# display.net
KiCad netlist of a schematic drawn in EAGLE
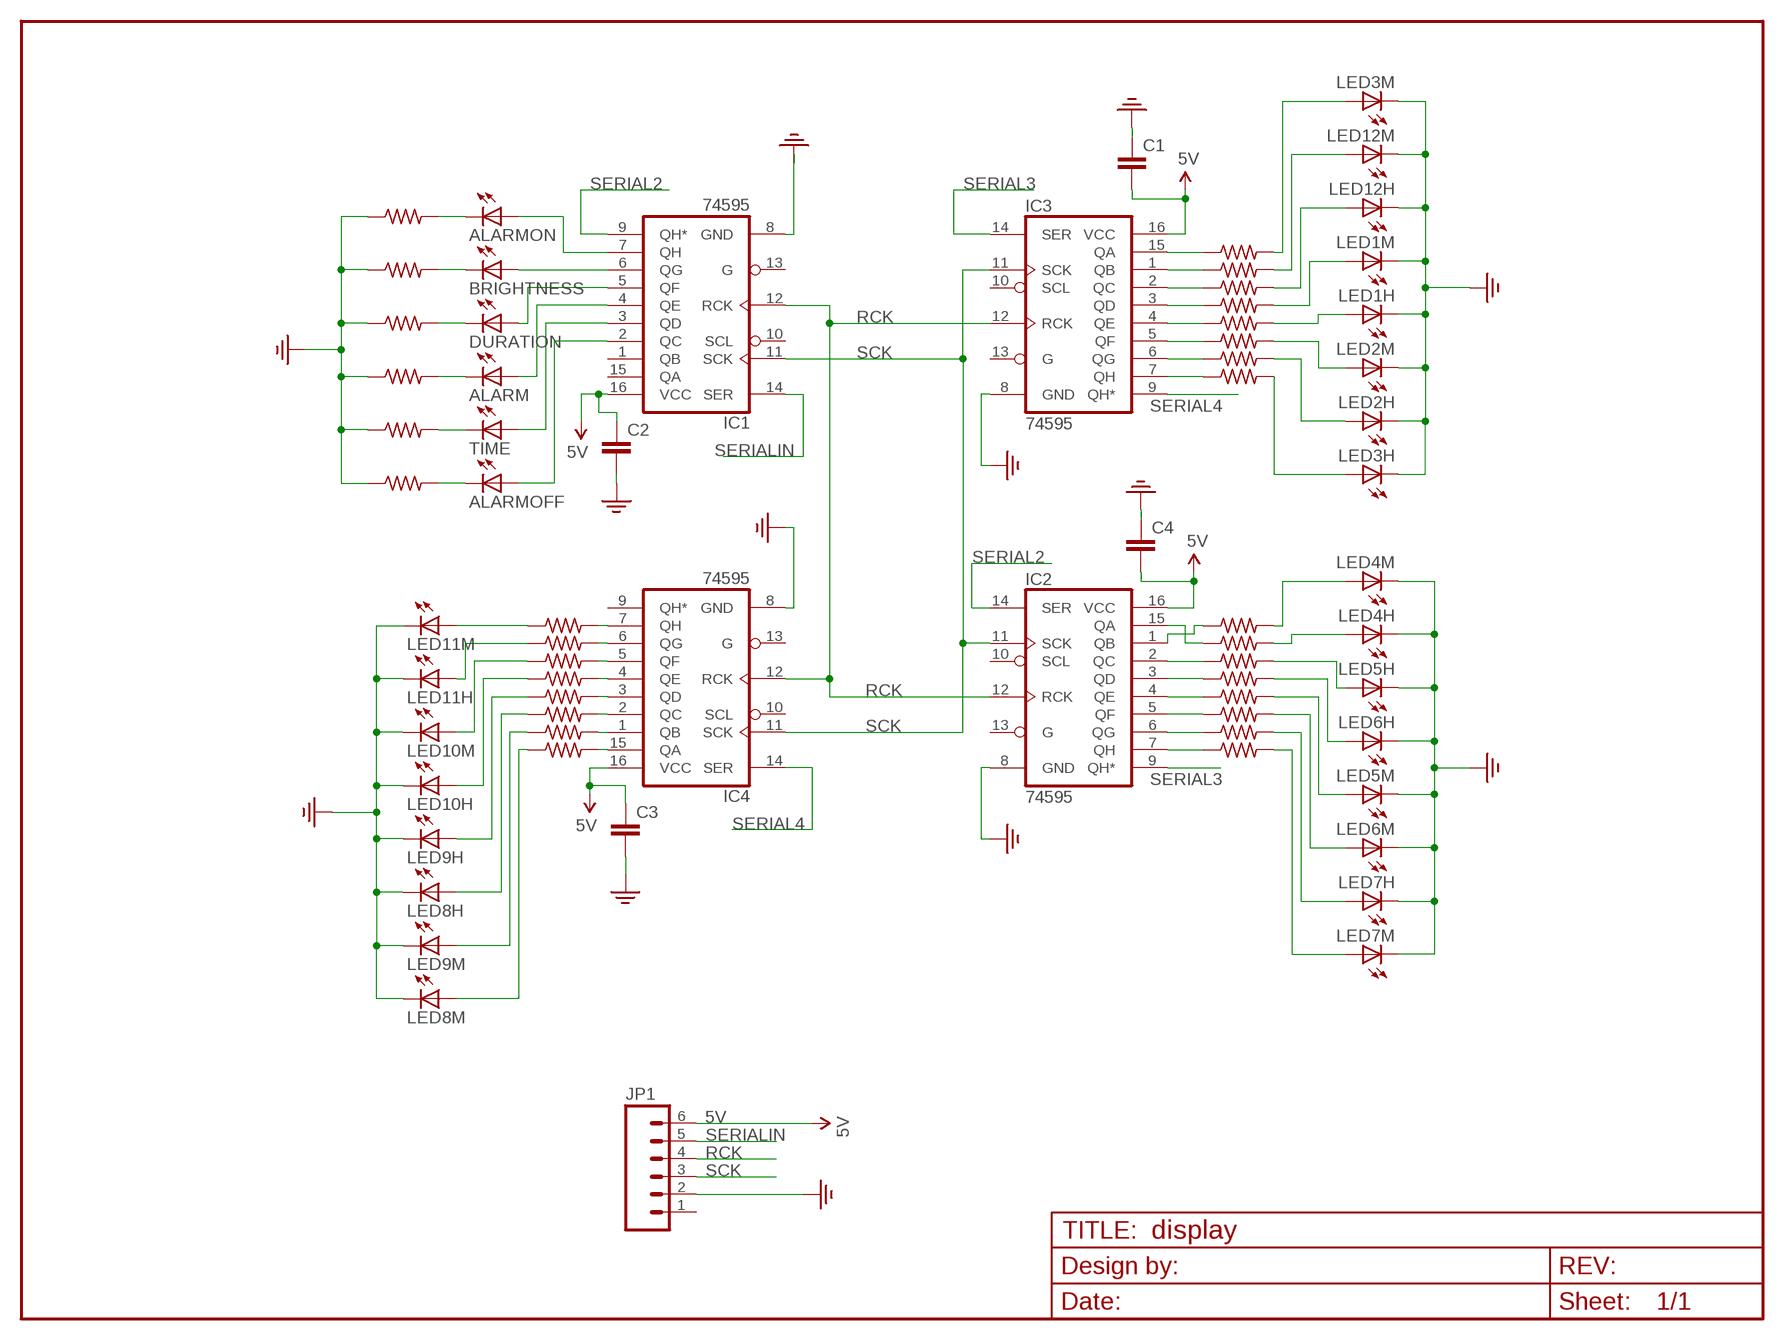
[diagram p0: schematic, sheet 1]

(export (version "E")
  (design (tool "Eeschema 10.0.6"))
  (components
    (comp (ref "ALARM")
      (value "LED1206")
      (footprint "eagle-import:LED-1206")
      (libsource (lib "eagle-import") (part "LED1206"))
    )
    (comp (ref "ALARMOFF")
      (value "LED1206")
      (footprint "eagle-import:LED-1206")
      (libsource (lib "eagle-import") (part "LED1206"))
    )
    (comp (ref "ALARMON")
      (value "LED1206")
      (footprint "eagle-import:LED-1206")
      (libsource (lib "eagle-import") (part "LED1206"))
    )
    (comp (ref "BRIGHTNESS")
      (value "LED1206")
      (footprint "eagle-import:LED-1206")
      (libsource (lib "eagle-import") (part "LED1206"))
    )
    (comp (ref "C1")
      (value "CAP0805")
      (footprint "eagle-import:0805")
      (libsource (lib "eagle-import") (part "CAP0805"))
    )
    (comp (ref "C2")
      (value "CAP0805")
      (footprint "eagle-import:0805")
      (libsource (lib "eagle-import") (part "CAP0805"))
    )
    (comp (ref "C3")
      (value "CAP0805")
      (footprint "eagle-import:0805")
      (libsource (lib "eagle-import") (part "CAP0805"))
    )
    (comp (ref "C4")
      (value "CAP0805")
      (footprint "eagle-import:0805")
      (libsource (lib "eagle-import") (part "CAP0805"))
    )
    (comp (ref "DURATION")
      (value "LED1206")
      (footprint "eagle-import:LED-1206")
      (libsource (lib "eagle-import") (part "LED1206"))
    )
    (comp (ref "FRAME1")
      (value "FRAME-LETTER")
      (footprint "eagle-import:CREATIVE_COMMONS")
      (libsource (lib "eagle-import") (part "FRAME-LETTER"))
    )
    (comp (ref "IC1")
      (value "74595")
      (footprint "eagle-import:TSSOP16")
      (libsource (lib "eagle-import") (part "74595"))
    )
    (comp (ref "IC2")
      (value "74595")
      (footprint "eagle-import:TSSOP16")
      (libsource (lib "eagle-import") (part "74595"))
    )
    (comp (ref "IC3")
      (value "74595")
      (footprint "eagle-import:TSSOP16")
      (libsource (lib "eagle-import") (part "74595"))
    )
    (comp (ref "IC4")
      (value "74595")
      (footprint "eagle-import:TSSOP16")
      (libsource (lib "eagle-import") (part "74595"))
    )
    (comp (ref "JP1")
      (value "M06SIP")
      (footprint "eagle-import:1X06")
      (libsource (lib "eagle-import") (part "M06SIP"))
    )
    (comp (ref "LED1H")
      (value "LED1206")
      (footprint "eagle-import:LED-1206")
      (libsource (lib "eagle-import") (part "LED1206"))
    )
    (comp (ref "LED1M")
      (value "LED1206")
      (footprint "eagle-import:LED-1206")
      (libsource (lib "eagle-import") (part "LED1206"))
    )
    (comp (ref "LED2H")
      (value "LED1206")
      (footprint "eagle-import:LED-1206")
      (libsource (lib "eagle-import") (part "LED1206"))
    )
    (comp (ref "LED2M")
      (value "LED1206")
      (footprint "eagle-import:LED-1206")
      (libsource (lib "eagle-import") (part "LED1206"))
    )
    (comp (ref "LED3H")
      (value "LED1206")
      (footprint "eagle-import:LED-1206")
      (libsource (lib "eagle-import") (part "LED1206"))
    )
    (comp (ref "LED3M")
      (value "LED1206")
      (footprint "eagle-import:LED-1206")
      (libsource (lib "eagle-import") (part "LED1206"))
    )
    (comp (ref "LED4H")
      (value "LED1206")
      (footprint "eagle-import:LED-1206")
      (libsource (lib "eagle-import") (part "LED1206"))
    )
    (comp (ref "LED4M")
      (value "LED1206")
      (footprint "eagle-import:LED-1206")
      (libsource (lib "eagle-import") (part "LED1206"))
    )
    (comp (ref "LED5H")
      (value "LED1206")
      (footprint "eagle-import:LED-1206")
      (libsource (lib "eagle-import") (part "LED1206"))
    )
    (comp (ref "LED5M")
      (value "LED1206")
      (footprint "eagle-import:LED-1206")
      (libsource (lib "eagle-import") (part "LED1206"))
    )
    (comp (ref "LED6H")
      (value "LED1206")
      (footprint "eagle-import:LED-1206")
      (libsource (lib "eagle-import") (part "LED1206"))
    )
    (comp (ref "LED6M")
      (value "LED1206")
      (footprint "eagle-import:LED-1206")
      (libsource (lib "eagle-import") (part "LED1206"))
    )
    (comp (ref "LED7H")
      (value "LED1206")
      (footprint "eagle-import:LED-1206")
      (libsource (lib "eagle-import") (part "LED1206"))
    )
    (comp (ref "LED7M")
      (value "LED1206")
      (footprint "eagle-import:LED-1206")
      (libsource (lib "eagle-import") (part "LED1206"))
    )
    (comp (ref "LED8H")
      (value "LED1206")
      (footprint "eagle-import:LED-1206")
      (libsource (lib "eagle-import") (part "LED1206"))
    )
    (comp (ref "LED8M")
      (value "LED1206")
      (footprint "eagle-import:LED-1206")
      (libsource (lib "eagle-import") (part "LED1206"))
    )
    (comp (ref "LED9H")
      (value "LED1206")
      (footprint "eagle-import:LED-1206")
      (libsource (lib "eagle-import") (part "LED1206"))
    )
    (comp (ref "LED9M")
      (value "LED1206")
      (footprint "eagle-import:LED-1206")
      (libsource (lib "eagle-import") (part "LED1206"))
    )
    (comp (ref "LED10H")
      (value "LED1206")
      (footprint "eagle-import:LED-1206")
      (libsource (lib "eagle-import") (part "LED1206"))
    )
    (comp (ref "LED10M")
      (value "LED1206")
      (footprint "eagle-import:LED-1206")
      (libsource (lib "eagle-import") (part "LED1206"))
    )
    (comp (ref "LED11H")
      (value "LED1206")
      (footprint "eagle-import:LED-1206")
      (libsource (lib "eagle-import") (part "LED1206"))
    )
    (comp (ref "LED11M")
      (value "LED1206")
      (footprint "eagle-import:LED-1206")
      (libsource (lib "eagle-import") (part "LED1206"))
    )
    (comp (ref "LED12H")
      (value "LED1206")
      (footprint "eagle-import:LED-1206")
      (libsource (lib "eagle-import") (part "LED1206"))
    )
    (comp (ref "LED12M")
      (value "LED1206")
      (footprint "eagle-import:LED-1206")
      (libsource (lib "eagle-import") (part "LED1206"))
    )
    (comp (ref "TIME")
      (value "LED1206")
      (footprint "eagle-import:LED-1206")
      (libsource (lib "eagle-import") (part "LED1206"))
    )
    (comp (ref "U$2")
      (value "RESISTOR")
      (footprint "eagle-import:RESISTOR-0805")
      (libsource (lib "eagle-import") (part "RESISTOR"))
    )
    (comp (ref "U$3")
      (value "RESISTOR")
      (footprint "eagle-import:RESISTOR-0805")
      (libsource (lib "eagle-import") (part "RESISTOR"))
    )
    (comp (ref "U$6")
      (value "RESISTOR")
      (footprint "eagle-import:RESISTOR-0805")
      (libsource (lib "eagle-import") (part "RESISTOR"))
    )
    (comp (ref "U$7")
      (value "RESISTOR")
      (footprint "eagle-import:RESISTOR-0805")
      (libsource (lib "eagle-import") (part "RESISTOR"))
    )
    (comp (ref "U$8")
      (value "RESISTOR")
      (footprint "eagle-import:RESISTOR-0805")
      (libsource (lib "eagle-import") (part "RESISTOR"))
    )
    (comp (ref "U$9")
      (value "RESISTOR")
      (footprint "eagle-import:RESISTOR-0805")
      (libsource (lib "eagle-import") (part "RESISTOR"))
    )
    (comp (ref "U$10")
      (value "RESISTOR")
      (footprint "eagle-import:RESISTOR-0805")
      (libsource (lib "eagle-import") (part "RESISTOR"))
    )
    (comp (ref "U$11")
      (value "RESISTOR")
      (footprint "eagle-import:RESISTOR-0805")
      (libsource (lib "eagle-import") (part "RESISTOR"))
    )
    (comp (ref "U$12")
      (value "RESISTOR")
      (footprint "eagle-import:RESISTOR-0805")
      (libsource (lib "eagle-import") (part "RESISTOR"))
    )
    (comp (ref "U$13")
      (value "RESISTOR")
      (footprint "eagle-import:RESISTOR-0805")
      (libsource (lib "eagle-import") (part "RESISTOR"))
    )
    (comp (ref "U$14")
      (value "RESISTOR")
      (footprint "eagle-import:RESISTOR-0805")
      (libsource (lib "eagle-import") (part "RESISTOR"))
    )
    (comp (ref "U$15")
      (value "RESISTOR")
      (footprint "eagle-import:RESISTOR-0805")
      (libsource (lib "eagle-import") (part "RESISTOR"))
    )
    (comp (ref "U$16")
      (value "RESISTOR")
      (footprint "eagle-import:RESISTOR-0805")
      (libsource (lib "eagle-import") (part "RESISTOR"))
    )
    (comp (ref "U$17")
      (value "RESISTOR")
      (footprint "eagle-import:RESISTOR-0805")
      (libsource (lib "eagle-import") (part "RESISTOR"))
    )
    (comp (ref "U$18")
      (value "RESISTOR")
      (footprint "eagle-import:RESISTOR-0805")
      (libsource (lib "eagle-import") (part "RESISTOR"))
    )
    (comp (ref "U$19")
      (value "RESISTOR")
      (footprint "eagle-import:RESISTOR-0805")
      (libsource (lib "eagle-import") (part "RESISTOR"))
    )
    (comp (ref "U$20")
      (value "RESISTOR")
      (footprint "eagle-import:RESISTOR-0805")
      (libsource (lib "eagle-import") (part "RESISTOR"))
    )
    (comp (ref "U$21")
      (value "RESISTOR")
      (footprint "eagle-import:RESISTOR-0805")
      (libsource (lib "eagle-import") (part "RESISTOR"))
    )
    (comp (ref "U$22")
      (value "RESISTOR")
      (footprint "eagle-import:RESISTOR-0805")
      (libsource (lib "eagle-import") (part "RESISTOR"))
    )
    (comp (ref "U$23")
      (value "RESISTOR")
      (footprint "eagle-import:RESISTOR-0805")
      (libsource (lib "eagle-import") (part "RESISTOR"))
    )
    (comp (ref "U$24")
      (value "RESISTOR")
      (footprint "eagle-import:RESISTOR-0805")
      (libsource (lib "eagle-import") (part "RESISTOR"))
    )
    (comp (ref "U$25")
      (value "RESISTOR")
      (footprint "eagle-import:RESISTOR-0805")
      (libsource (lib "eagle-import") (part "RESISTOR"))
    )
    (comp (ref "U$26")
      (value "RESISTOR")
      (footprint "eagle-import:RESISTOR-0805")
      (libsource (lib "eagle-import") (part "RESISTOR"))
    )
    (comp (ref "U$27")
      (value "RESISTOR")
      (footprint "eagle-import:RESISTOR-0805")
      (libsource (lib "eagle-import") (part "RESISTOR"))
    )
    (comp (ref "U$28")
      (value "RESISTOR")
      (footprint "eagle-import:RESISTOR-0805")
      (libsource (lib "eagle-import") (part "RESISTOR"))
    )
    (comp (ref "U$29")
      (value "RESISTOR")
      (footprint "eagle-import:RESISTOR-0805")
      (libsource (lib "eagle-import") (part "RESISTOR"))
    )
    (comp (ref "U$30")
      (value "RESISTOR")
      (footprint "eagle-import:RESISTOR-0805")
      (libsource (lib "eagle-import") (part "RESISTOR"))
    )
    (comp (ref "U$31")
      (value "RESISTOR")
      (footprint "eagle-import:RESISTOR-0805")
      (libsource (lib "eagle-import") (part "RESISTOR"))
    )
    (comp (ref "U$32")
      (value "RESISTOR")
      (footprint "eagle-import:RESISTOR-0805")
      (libsource (lib "eagle-import") (part "RESISTOR"))
    )
    (comp (ref "U$33")
      (value "RESISTOR")
      (footprint "eagle-import:RESISTOR-0805")
      (libsource (lib "eagle-import") (part "RESISTOR"))
    )
  )
  (nets
    (net (code "1") (name "/RCK") (class "Default")
      (node (ref "IC1") (pin "12") (pinfunction "RCK_12") (pintype "input"))
      (node (ref "IC2") (pin "12") (pinfunction "RCK_12") (pintype "input"))
      (node (ref "IC3") (pin "12") (pinfunction "RCK_12") (pintype "input"))
      (node (ref "IC4") (pin "12") (pinfunction "RCK_12") (pintype "input"))
      (node (ref "JP1") (pin "4") (pinfunction "4_4") (pintype "passive"))
    )
    (net (code "2") (name "/SCK") (class "Default")
      (node (ref "IC1") (pin "11") (pinfunction "SCK_11") (pintype "input"))
      (node (ref "IC2") (pin "11") (pinfunction "SCK_11") (pintype "input"))
      (node (ref "IC3") (pin "11") (pinfunction "SCK_11") (pintype "input"))
      (node (ref "IC4") (pin "11") (pinfunction "SCK_11") (pintype "input"))
      (node (ref "JP1") (pin "3") (pinfunction "3_3") (pintype "passive"))
    )
    (net (code "3") (name "/SERIAL2") (class "Default")
      (node (ref "IC1") (pin "9") (pinfunction "QH*_9") (pintype "output"))
      (node (ref "IC2") (pin "14") (pinfunction "SER_14") (pintype "input"))
    )
    (net (code "4") (name "/SERIAL3") (class "Default")
      (node (ref "IC2") (pin "9") (pinfunction "QH*_9") (pintype "output"))
      (node (ref "IC3") (pin "14") (pinfunction "SER_14") (pintype "input"))
    )
    (net (code "5") (name "/SERIAL4") (class "Default")
      (node (ref "IC3") (pin "9") (pinfunction "QH*_9") (pintype "output"))
      (node (ref "IC4") (pin "14") (pinfunction "SER_14") (pintype "input"))
    )
    (net (code "6") (name "/SERIALIN") (class "Default")
      (node (ref "IC1") (pin "14") (pinfunction "SER_14") (pintype "input"))
      (node (ref "JP1") (pin "5") (pinfunction "5_5") (pintype "passive"))
    )
    (net (code "7") (name "5V") (class "Default")
      (node (ref "C1") (pin "2") (pinfunction "2_2") (pintype "passive"))
      (node (ref "C2") (pin "1") (pinfunction "1_1") (pintype "passive"))
      (node (ref "C3") (pin "1") (pinfunction "1_1") (pintype "passive"))
      (node (ref "C4") (pin "2") (pinfunction "2_2") (pintype "passive"))
      (node (ref "IC1") (pin "16") (pinfunction "VCC_16") (pintype "power_in"))
      (node (ref "IC2") (pin "16") (pinfunction "VCC_16") (pintype "power_in"))
      (node (ref "IC3") (pin "16") (pinfunction "VCC_16") (pintype "power_in"))
      (node (ref "IC4") (pin "16") (pinfunction "VCC_16") (pintype "power_in"))
      (node (ref "JP1") (pin "6") (pinfunction "6_6") (pintype "passive"))
    )
    (net (code "8") (name "GND2") (class "Default")
      (node (ref "C1") (pin "1") (pinfunction "1_1") (pintype "passive"))
      (node (ref "C2") (pin "2") (pinfunction "2_2") (pintype "passive"))
      (node (ref "C3") (pin "2") (pinfunction "2_2") (pintype "passive"))
      (node (ref "C4") (pin "1") (pinfunction "1_1") (pintype "passive"))
      (node (ref "IC1") (pin "8") (pinfunction "GND_8") (pintype "power_in"))
      (node (ref "IC2") (pin "8") (pinfunction "GND_8") (pintype "power_in"))
      (node (ref "IC3") (pin "8") (pinfunction "GND_8") (pintype "power_in"))
      (node (ref "IC4") (pin "8") (pinfunction "GND_8") (pintype "power_in"))
      (node (ref "JP1") (pin "2") (pinfunction "2_2") (pintype "passive"))
      (node (ref "LED10H") (pin "C") (pinfunction "C_C") (pintype "passive"))
      (node (ref "LED10M") (pin "C") (pinfunction "C_C") (pintype "passive"))
      (node (ref "LED11H") (pin "C") (pinfunction "C_C") (pintype "passive"))
      (node (ref "LED11M") (pin "C") (pinfunction "C_C") (pintype "passive"))
      (node (ref "LED12H") (pin "C") (pinfunction "C_C") (pintype "passive"))
      (node (ref "LED12M") (pin "C") (pinfunction "C_C") (pintype "passive"))
      (node (ref "LED1H") (pin "C") (pinfunction "C_C") (pintype "passive"))
      (node (ref "LED1M") (pin "C") (pinfunction "C_C") (pintype "passive"))
      (node (ref "LED2H") (pin "C") (pinfunction "C_C") (pintype "passive"))
      (node (ref "LED2M") (pin "C") (pinfunction "C_C") (pintype "passive"))
      (node (ref "LED3H") (pin "C") (pinfunction "C_C") (pintype "passive"))
      (node (ref "LED3M") (pin "C") (pinfunction "C_C") (pintype "passive"))
      (node (ref "LED4H") (pin "C") (pinfunction "C_C") (pintype "passive"))
      (node (ref "LED4M") (pin "C") (pinfunction "C_C") (pintype "passive"))
      (node (ref "LED5H") (pin "C") (pinfunction "C_C") (pintype "passive"))
      (node (ref "LED5M") (pin "C") (pinfunction "C_C") (pintype "passive"))
      (node (ref "LED6H") (pin "C") (pinfunction "C_C") (pintype "passive"))
      (node (ref "LED6M") (pin "C") (pinfunction "C_C") (pintype "passive"))
      (node (ref "LED7H") (pin "C") (pinfunction "C_C") (pintype "passive"))
      (node (ref "LED7M") (pin "C") (pinfunction "C_C") (pintype "passive"))
      (node (ref "LED8H") (pin "C") (pinfunction "C_C") (pintype "passive"))
      (node (ref "LED8M") (pin "C") (pinfunction "C_C") (pintype "passive"))
      (node (ref "LED9H") (pin "C") (pinfunction "C_C") (pintype "passive"))
      (node (ref "LED9M") (pin "C") (pinfunction "C_C") (pintype "passive"))
      (node (ref "U$24") (pin "1") (pinfunction "1_1") (pintype "passive"))
      (node (ref "U$25") (pin "1") (pinfunction "1_1") (pintype "passive"))
      (node (ref "U$30") (pin "1") (pinfunction "1_1") (pintype "passive"))
      (node (ref "U$31") (pin "1") (pinfunction "1_1") (pintype "passive"))
      (node (ref "U$32") (pin "1") (pinfunction "1_1") (pintype "passive"))
      (node (ref "U$33") (pin "1") (pinfunction "1_1") (pintype "passive"))
    )
    (net (code "9") (name "Net-(ALARM-PadC)") (class "Default")
      (node (ref "ALARM") (pin "C") (pinfunction "C_C") (pintype "passive"))
      (node (ref "U$31") (pin "2") (pinfunction "2_2") (pintype "passive"))
    )
    (net (code "10") (name "Net-(ALARMOFF-PadC)") (class "Default")
      (node (ref "ALARMOFF") (pin "C") (pinfunction "C_C") (pintype "passive"))
      (node (ref "U$33") (pin "2") (pinfunction "2_2") (pintype "passive"))
    )
    (net (code "11") (name "Net-(ALARMON-PadC)") (class "Default")
      (node (ref "ALARMON") (pin "C") (pinfunction "C_C") (pintype "passive"))
      (node (ref "U$24") (pin "2") (pinfunction "2_2") (pintype "passive"))
    )
    (net (code "12") (name "Net-(BRIGHTNESS-PadC)") (class "Default")
      (node (ref "BRIGHTNESS") (pin "C") (pinfunction "C_C") (pintype "passive"))
      (node (ref "U$25") (pin "2") (pinfunction "2_2") (pintype "passive"))
    )
    (net (code "13") (name "Net-(DURATION-PadC)") (class "Default")
      (node (ref "DURATION") (pin "C") (pinfunction "C_C") (pintype "passive"))
      (node (ref "U$30") (pin "2") (pinfunction "2_2") (pintype "passive"))
    )
    (net (code "14") (name "Net-(IC1-QC)") (class "Default")
      (node (ref "ALARMOFF") (pin "A") (pinfunction "A_A") (pintype "passive"))
      (node (ref "IC1") (pin "2") (pinfunction "QC_2") (pintype "tri_state"))
    )
    (net (code "15") (name "Net-(IC1-QD)") (class "Default")
      (node (ref "IC1") (pin "3") (pinfunction "QD_3") (pintype "tri_state"))
      (node (ref "TIME") (pin "A") (pinfunction "A_A") (pintype "passive"))
    )
    (net (code "16") (name "Net-(IC1-QE)") (class "Default")
      (node (ref "ALARM") (pin "A") (pinfunction "A_A") (pintype "passive"))
      (node (ref "IC1") (pin "4") (pinfunction "QE_4") (pintype "tri_state"))
    )
    (net (code "17") (name "Net-(IC1-QF)") (class "Default")
      (node (ref "DURATION") (pin "A") (pinfunction "A_A") (pintype "passive"))
      (node (ref "IC1") (pin "5") (pinfunction "QF_5") (pintype "tri_state"))
    )
    (net (code "18") (name "Net-(IC1-QG)") (class "Default")
      (node (ref "BRIGHTNESS") (pin "A") (pinfunction "A_A") (pintype "passive"))
      (node (ref "IC1") (pin "6") (pinfunction "QG_6") (pintype "tri_state"))
    )
    (net (code "19") (name "Net-(IC1-QH)") (class "Default")
      (node (ref "ALARMON") (pin "A") (pinfunction "A_A") (pintype "passive"))
      (node (ref "IC1") (pin "7") (pinfunction "QH_7") (pintype "tri_state"))
    )
    (net (code "20") (name "Net-(IC2-QA)") (class "Default")
      (node (ref "IC2") (pin "15") (pinfunction "QA_15") (pintype "tri_state"))
      (node (ref "U$21") (pin "1") (pinfunction "1_1") (pintype "passive"))
    )
    (net (code "21") (name "Net-(IC2-QB)") (class "Default")
      (node (ref "IC2") (pin "1") (pinfunction "QB_1") (pintype "tri_state"))
      (node (ref "U$20") (pin "1") (pinfunction "1_1") (pintype "passive"))
    )
    (net (code "22") (name "Net-(IC2-QC)") (class "Default")
      (node (ref "IC2") (pin "2") (pinfunction "QC_2") (pintype "tri_state"))
      (node (ref "U$22") (pin "1") (pinfunction "1_1") (pintype "passive"))
    )
    (net (code "23") (name "Net-(IC2-QD)") (class "Default")
      (node (ref "IC2") (pin "3") (pinfunction "QD_3") (pintype "tri_state"))
      (node (ref "U$23") (pin "1") (pinfunction "1_1") (pintype "passive"))
    )
    (net (code "24") (name "Net-(IC2-QE)") (class "Default")
      (node (ref "IC2") (pin "4") (pinfunction "QE_4") (pintype "tri_state"))
      (node (ref "U$26") (pin "1") (pinfunction "1_1") (pintype "passive"))
    )
    (net (code "25") (name "Net-(IC2-QF)") (class "Default")
      (node (ref "IC2") (pin "5") (pinfunction "QF_5") (pintype "tri_state"))
      (node (ref "U$27") (pin "1") (pinfunction "1_1") (pintype "passive"))
    )
    (net (code "26") (name "Net-(IC2-QG)") (class "Default")
      (node (ref "IC2") (pin "6") (pinfunction "QG_6") (pintype "tri_state"))
      (node (ref "U$28") (pin "1") (pinfunction "1_1") (pintype "passive"))
    )
    (net (code "27") (name "Net-(IC2-QH)") (class "Default")
      (node (ref "IC2") (pin "7") (pinfunction "QH_7") (pintype "tri_state"))
      (node (ref "U$29") (pin "1") (pinfunction "1_1") (pintype "passive"))
    )
    (net (code "28") (name "Net-(IC3-QA)") (class "Default")
      (node (ref "IC3") (pin "15") (pinfunction "QA_15") (pintype "tri_state"))
      (node (ref "U$6") (pin "1") (pinfunction "1_1") (pintype "passive"))
    )
    (net (code "29") (name "Net-(IC3-QB)") (class "Default")
      (node (ref "IC3") (pin "1") (pinfunction "QB_1") (pintype "tri_state"))
      (node (ref "U$7") (pin "1") (pinfunction "1_1") (pintype "passive"))
    )
    (net (code "30") (name "Net-(IC3-QC)") (class "Default")
      (node (ref "IC3") (pin "2") (pinfunction "QC_2") (pintype "tri_state"))
      (node (ref "U$8") (pin "1") (pinfunction "1_1") (pintype "passive"))
    )
    (net (code "31") (name "Net-(IC3-QD)") (class "Default")
      (node (ref "IC3") (pin "3") (pinfunction "QD_3") (pintype "tri_state"))
      (node (ref "U$9") (pin "1") (pinfunction "1_1") (pintype "passive"))
    )
    (net (code "32") (name "Net-(IC3-QE)") (class "Default")
      (node (ref "IC3") (pin "4") (pinfunction "QE_4") (pintype "tri_state"))
      (node (ref "U$10") (pin "1") (pinfunction "1_1") (pintype "passive"))
    )
    (net (code "33") (name "Net-(IC3-QF)") (class "Default")
      (node (ref "IC3") (pin "5") (pinfunction "QF_5") (pintype "tri_state"))
      (node (ref "U$11") (pin "1") (pinfunction "1_1") (pintype "passive"))
    )
    (net (code "34") (name "Net-(IC3-QG)") (class "Default")
      (node (ref "IC3") (pin "6") (pinfunction "QG_6") (pintype "tri_state"))
      (node (ref "U$13") (pin "1") (pinfunction "1_1") (pintype "passive"))
    )
    (net (code "35") (name "Net-(IC3-QH)") (class "Default")
      (node (ref "IC3") (pin "7") (pinfunction "QH_7") (pintype "tri_state"))
      (node (ref "U$12") (pin "1") (pinfunction "1_1") (pintype "passive"))
    )
    (net (code "36") (name "Net-(IC4-QA)") (class "Default")
      (node (ref "IC4") (pin "15") (pinfunction "QA_15") (pintype "tri_state"))
      (node (ref "U$2") (pin "2") (pinfunction "2_2") (pintype "passive"))
    )
    (net (code "37") (name "Net-(IC4-QB)") (class "Default")
      (node (ref "IC4") (pin "1") (pinfunction "QB_1") (pintype "tri_state"))
      (node (ref "U$3") (pin "2") (pinfunction "2_2") (pintype "passive"))
    )
    (net (code "38") (name "Net-(IC4-QC)") (class "Default")
      (node (ref "IC4") (pin "2") (pinfunction "QC_2") (pintype "tri_state"))
      (node (ref "U$14") (pin "2") (pinfunction "2_2") (pintype "passive"))
    )
    (net (code "39") (name "Net-(IC4-QD)") (class "Default")
      (node (ref "IC4") (pin "3") (pinfunction "QD_3") (pintype "tri_state"))
      (node (ref "U$15") (pin "2") (pinfunction "2_2") (pintype "passive"))
    )
    (net (code "40") (name "Net-(IC4-QE)") (class "Default")
      (node (ref "IC4") (pin "4") (pinfunction "QE_4") (pintype "tri_state"))
      (node (ref "U$19") (pin "2") (pinfunction "2_2") (pintype "passive"))
    )
    (net (code "41") (name "Net-(IC4-QF)") (class "Default")
      (node (ref "IC4") (pin "5") (pinfunction "QF_5") (pintype "tri_state"))
      (node (ref "U$16") (pin "2") (pinfunction "2_2") (pintype "passive"))
    )
    (net (code "42") (name "Net-(IC4-QG)") (class "Default")
      (node (ref "IC4") (pin "6") (pinfunction "QG_6") (pintype "tri_state"))
      (node (ref "U$17") (pin "2") (pinfunction "2_2") (pintype "passive"))
    )
    (net (code "43") (name "Net-(IC4-QH)") (class "Default")
      (node (ref "IC4") (pin "7") (pinfunction "QH_7") (pintype "tri_state"))
      (node (ref "U$18") (pin "2") (pinfunction "2_2") (pintype "passive"))
    )
    (net (code "44") (name "Net-(LED1H-PadA)") (class "Default")
      (node (ref "LED1H") (pin "A") (pinfunction "A_A") (pintype "passive"))
      (node (ref "U$10") (pin "2") (pinfunction "2_2") (pintype "passive"))
    )
    (net (code "45") (name "Net-(LED1M-PadA)") (class "Default")
      (node (ref "LED1M") (pin "A") (pinfunction "A_A") (pintype "passive"))
      (node (ref "U$9") (pin "2") (pinfunction "2_2") (pintype "passive"))
    )
    (net (code "46") (name "Net-(LED2H-PadA)") (class "Default")
      (node (ref "LED2H") (pin "A") (pinfunction "A_A") (pintype "passive"))
      (node (ref "U$13") (pin "2") (pinfunction "2_2") (pintype "passive"))
    )
    (net (code "47") (name "Net-(LED2M-PadA)") (class "Default")
      (node (ref "LED2M") (pin "A") (pinfunction "A_A") (pintype "passive"))
      (node (ref "U$11") (pin "2") (pinfunction "2_2") (pintype "passive"))
    )
    (net (code "48") (name "Net-(LED3H-PadA)") (class "Default")
      (node (ref "LED3H") (pin "A") (pinfunction "A_A") (pintype "passive"))
      (node (ref "U$12") (pin "2") (pinfunction "2_2") (pintype "passive"))
    )
    (net (code "49") (name "Net-(LED3M-PadA)") (class "Default")
      (node (ref "LED3M") (pin "A") (pinfunction "A_A") (pintype "passive"))
      (node (ref "U$6") (pin "2") (pinfunction "2_2") (pintype "passive"))
    )
    (net (code "50") (name "Net-(LED4H-PadA)") (class "Default")
      (node (ref "LED4H") (pin "A") (pinfunction "A_A") (pintype "passive"))
      (node (ref "U$21") (pin "2") (pinfunction "2_2") (pintype "passive"))
    )
    (net (code "51") (name "Net-(LED4M-PadA)") (class "Default")
      (node (ref "LED4M") (pin "A") (pinfunction "A_A") (pintype "passive"))
      (node (ref "U$20") (pin "2") (pinfunction "2_2") (pintype "passive"))
    )
    (net (code "52") (name "Net-(LED5H-PadA)") (class "Default")
      (node (ref "LED5H") (pin "A") (pinfunction "A_A") (pintype "passive"))
      (node (ref "U$22") (pin "2") (pinfunction "2_2") (pintype "passive"))
    )
    (net (code "53") (name "Net-(LED5M-PadA)") (class "Default")
      (node (ref "LED5M") (pin "A") (pinfunction "A_A") (pintype "passive"))
      (node (ref "U$26") (pin "2") (pinfunction "2_2") (pintype "passive"))
    )
    (net (code "54") (name "Net-(LED6H-PadA)") (class "Default")
      (node (ref "LED6H") (pin "A") (pinfunction "A_A") (pintype "passive"))
      (node (ref "U$23") (pin "2") (pinfunction "2_2") (pintype "passive"))
    )
    (net (code "55") (name "Net-(LED6M-PadA)") (class "Default")
      (node (ref "LED6M") (pin "A") (pinfunction "A_A") (pintype "passive"))
      (node (ref "U$27") (pin "2") (pinfunction "2_2") (pintype "passive"))
    )
    (net (code "56") (name "Net-(LED7H-PadA)") (class "Default")
      (node (ref "LED7H") (pin "A") (pinfunction "A_A") (pintype "passive"))
      (node (ref "U$28") (pin "2") (pinfunction "2_2") (pintype "passive"))
    )
    (net (code "57") (name "Net-(LED7M-PadA)") (class "Default")
      (node (ref "LED7M") (pin "A") (pinfunction "A_A") (pintype "passive"))
      (node (ref "U$29") (pin "2") (pinfunction "2_2") (pintype "passive"))
    )
    (net (code "58") (name "Net-(LED8H-PadA)") (class "Default")
      (node (ref "LED8H") (pin "A") (pinfunction "A_A") (pintype "passive"))
      (node (ref "U$14") (pin "1") (pinfunction "1_1") (pintype "passive"))
    )
    (net (code "59") (name "Net-(LED8M-PadA)") (class "Default")
      (node (ref "LED8M") (pin "A") (pinfunction "A_A") (pintype "passive"))
      (node (ref "U$2") (pin "1") (pinfunction "1_1") (pintype "passive"))
    )
    (net (code "60") (name "Net-(LED9H-PadA)") (class "Default")
      (node (ref "LED9H") (pin "A") (pinfunction "A_A") (pintype "passive"))
      (node (ref "U$15") (pin "1") (pinfunction "1_1") (pintype "passive"))
    )
    (net (code "61") (name "Net-(LED9M-PadA)") (class "Default")
      (node (ref "LED9M") (pin "A") (pinfunction "A_A") (pintype "passive"))
      (node (ref "U$3") (pin "1") (pinfunction "1_1") (pintype "passive"))
    )
    (net (code "62") (name "Net-(LED10H-PadA)") (class "Default")
      (node (ref "LED10H") (pin "A") (pinfunction "A_A") (pintype "passive"))
      (node (ref "U$19") (pin "1") (pinfunction "1_1") (pintype "passive"))
    )
    (net (code "63") (name "Net-(LED10M-PadA)") (class "Default")
      (node (ref "LED10M") (pin "A") (pinfunction "A_A") (pintype "passive"))
      (node (ref "U$16") (pin "1") (pinfunction "1_1") (pintype "passive"))
    )
    (net (code "64") (name "Net-(LED11H-PadA)") (class "Default")
      (node (ref "LED11H") (pin "A") (pinfunction "A_A") (pintype "passive"))
      (node (ref "U$17") (pin "1") (pinfunction "1_1") (pintype "passive"))
    )
    (net (code "65") (name "Net-(LED11M-PadA)") (class "Default")
      (node (ref "LED11M") (pin "A") (pinfunction "A_A") (pintype "passive"))
      (node (ref "U$18") (pin "1") (pinfunction "1_1") (pintype "passive"))
    )
    (net (code "66") (name "Net-(LED12H-PadA)") (class "Default")
      (node (ref "LED12H") (pin "A") (pinfunction "A_A") (pintype "passive"))
      (node (ref "U$8") (pin "2") (pinfunction "2_2") (pintype "passive"))
    )
    (net (code "67") (name "Net-(LED12M-PadA)") (class "Default")
      (node (ref "LED12M") (pin "A") (pinfunction "A_A") (pintype "passive"))
      (node (ref "U$7") (pin "2") (pinfunction "2_2") (pintype "passive"))
    )
    (net (code "68") (name "Net-(TIME-PadC)") (class "Default")
      (node (ref "TIME") (pin "C") (pinfunction "C_C") (pintype "passive"))
      (node (ref "U$32") (pin "2") (pinfunction "2_2") (pintype "passive"))
    )
    (net (code "69") (name "unconnected-(IC1-G-Pad13)") (class "Default")
      (node (ref "IC1") (pin "13") (pinfunction "G_13") (pintype "input"))
    )
    (net (code "70") (name "unconnected-(IC1-QA-Pad15)") (class "Default")
      (node (ref "IC1") (pin "15") (pinfunction "QA_15") (pintype "tri_state"))
    )
    (net (code "71") (name "unconnected-(IC1-QB-Pad1)") (class "Default")
      (node (ref "IC1") (pin "1") (pinfunction "QB_1") (pintype "tri_state"))
    )
    (net (code "72") (name "unconnected-(IC1-SCL-Pad10)") (class "Default")
      (node (ref "IC1") (pin "10") (pinfunction "SCL_10") (pintype "input"))
    )
    (net (code "73") (name "unconnected-(IC2-G-Pad13)") (class "Default")
      (node (ref "IC2") (pin "13") (pinfunction "G_13") (pintype "input"))
    )
    (net (code "74") (name "unconnected-(IC2-SCL-Pad10)") (class "Default")
      (node (ref "IC2") (pin "10") (pinfunction "SCL_10") (pintype "input"))
    )
    (net (code "75") (name "unconnected-(IC3-G-Pad13)") (class "Default")
      (node (ref "IC3") (pin "13") (pinfunction "G_13") (pintype "input"))
    )
    (net (code "76") (name "unconnected-(IC3-SCL-Pad10)") (class "Default")
      (node (ref "IC3") (pin "10") (pinfunction "SCL_10") (pintype "input"))
    )
    (net (code "77") (name "unconnected-(IC4-G-Pad13)") (class "Default")
      (node (ref "IC4") (pin "13") (pinfunction "G_13") (pintype "input"))
    )
    (net (code "78") (name "unconnected-(IC4-QH*-Pad9)") (class "Default")
      (node (ref "IC4") (pin "9") (pinfunction "QH*_9") (pintype "output"))
    )
    (net (code "79") (name "unconnected-(IC4-SCL-Pad10)") (class "Default")
      (node (ref "IC4") (pin "10") (pinfunction "SCL_10") (pintype "input"))
    )
    (net (code "80") (name "unconnected-(JP1-Pad1)") (class "Default")
      (node (ref "JP1") (pin "1") (pinfunction "1_1") (pintype "passive"))
    )
  )
)
